# DE-211024_2.net
KiCad netlist of a schematic drawn in Altium Designer
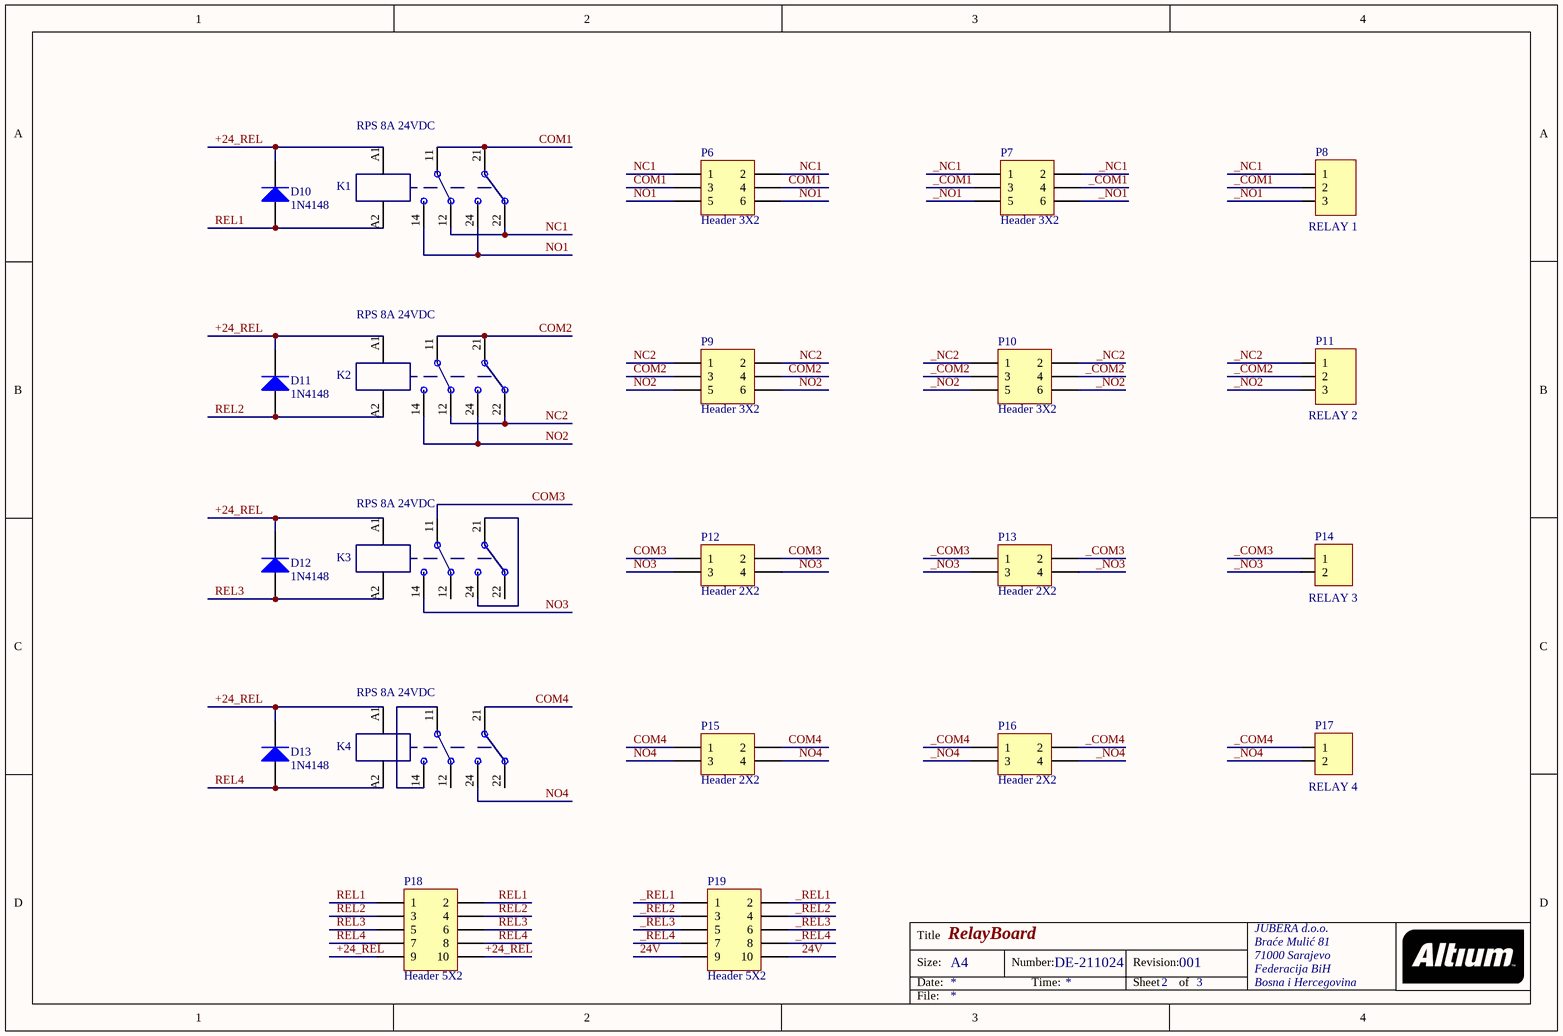
[diagram p0: DE-211024_2.SchDoc]

(export (version "E")
  (design (tool "Eeschema 10.0.6"))
  (components
    (comp (ref "D10")
      (value "1N4148")
      (footprint "SOD323")
      (description "General-purpose Diode")
      (fields (field (name "PUBLISHER") "Altium Limited"))
      (libsource (lib "DE-211024") (part "BAS321"))
    )
    (comp (ref "D11")
      (value "1N4148")
      (footprint "SOD323")
      (description "General-purpose Diode")
      (fields (field (name "PUBLISHER") "Altium Limited"))
      (libsource (lib "DE-211024") (part "BAS321"))
    )
    (comp (ref "D12")
      (value "1N4148")
      (footprint "SOD323")
      (description "General-purpose Diode")
      (fields (field (name "PUBLISHER") "Altium Limited"))
      (libsource (lib "DE-211024") (part "BAS321"))
    )
    (comp (ref "D13")
      (value "1N4148")
      (footprint "SOD323")
      (description "General-purpose Diode")
      (fields (field (name "PUBLISHER") "Altium Limited"))
      (libsource (lib "DE-211024") (part "BAS321"))
    )
    (comp (ref "K1")
      (value "RPS 8A 24VDC")
      (footprint "RPS 2CO 8A 24V")
      (libsource (lib "DE-211024") (part "PCB relay 2CO, 8A, 24VDC, RPS serie 5mm"))
    )
    (comp (ref "K2")
      (value "RPS 8A 24VDC")
      (footprint "RPS 2CO 8A 24V")
      (libsource (lib "DE-211024") (part "PCB relay 2CO, 8A, 24VDC, RPS serie 5mm"))
    )
    (comp (ref "K3")
      (value "RPS 8A 24VDC")
      (footprint "RPS 2CO 8A 24V")
      (libsource (lib "DE-211024") (part "PCB relay 2CO, 8A, 24VDC, RPS serie 5mm"))
    )
    (comp (ref "K4")
      (value "RPS 8A 24VDC")
      (footprint "RPS 2CO 8A 24V")
      (libsource (lib "DE-211024") (part "PCB relay 2CO, 8A, 24VDC, RPS serie 5mm"))
    )
    (comp (ref "P6")
      (value "Header 3X2")
      (footprint "HDR2X3")
      (description "Header, 3-Pin, Dual row")
      (fields (field (name "PUBLISHER") "Altium Limited"))
      (libsource (lib "Miscellaneous Connectors") (part "Header 3X2"))
    )
    (comp (ref "P7")
      (value "Header 3X2")
      (footprint "HDR2X3")
      (description "Header, 3-Pin, Dual row")
      (fields (field (name "PUBLISHER") "Altium Limited"))
      (libsource (lib "Miscellaneous Connectors") (part "Header 3X2"))
    )
    (comp (ref "P8")
      (value "RELAY 1")
      (footprint "TERMINAL BLOK 3")
      (description "3 pinski terminal blok konektor")
      (libsource (lib "DE-211024") (part "TERMINAL BLOK 3"))
    )
    (comp (ref "P9")
      (value "Header 3X2")
      (footprint "HDR2X3")
      (description "Header, 3-Pin, Dual row")
      (fields (field (name "PUBLISHER") "Altium Limited"))
      (libsource (lib "Miscellaneous Connectors") (part "Header 3X2"))
    )
    (comp (ref "P10")
      (value "Header 3X2")
      (footprint "HDR2X3")
      (description "Header, 3-Pin, Dual row")
      (fields (field (name "PUBLISHER") "Altium Limited"))
      (libsource (lib "Miscellaneous Connectors") (part "Header 3X2"))
    )
    (comp (ref "P11")
      (value "RELAY 2")
      (footprint "TERMINAL BLOK 3")
      (description "3 pinski terminal blok konektor")
      (libsource (lib "DE-211024") (part "TERMINAL BLOK 3"))
    )
    (comp (ref "P12")
      (value "Header 2X2")
      (footprint "HDR2X2")
      (description "Header, 2-Pin, Dual row")
      (fields (field (name "PUBLISHER") "Altium Limited"))
      (libsource (lib "Miscellaneous Connectors") (part "Header 2X2"))
    )
    (comp (ref "P13")
      (value "Header 2X2")
      (footprint "HDR2X2")
      (description "Header, 2-Pin, Dual row")
      (fields (field (name "PUBLISHER") "Altium Limited"))
      (libsource (lib "Miscellaneous Connectors") (part "Header 2X2"))
    )
    (comp (ref "P14")
      (value "RELAY 3")
      (footprint "TERMINAL BLOK 2")
      (description "Terminal blok konektor 3,5 mm")
      (libsource (lib "DE-211024") (part "TERMINAL BLOK 2"))
    )
    (comp (ref "P15")
      (value "Header 2X2")
      (footprint "HDR2X2")
      (description "Header, 2-Pin, Dual row")
      (fields (field (name "PUBLISHER") "Altium Limited"))
      (libsource (lib "Miscellaneous Connectors") (part "Header 2X2"))
    )
    (comp (ref "P16")
      (value "Header 2X2")
      (footprint "HDR2X2")
      (description "Header, 2-Pin, Dual row")
      (fields (field (name "PUBLISHER") "Altium Limited"))
      (libsource (lib "Miscellaneous Connectors") (part "Header 2X2"))
    )
    (comp (ref "P17")
      (value "RELAY 4")
      (footprint "TERMINAL BLOK 2")
      (description "Terminal blok konektor 3,5 mm")
      (libsource (lib "DE-211024") (part "TERMINAL BLOK 2"))
    )
    (comp (ref "P18")
      (value "Header 5X2")
      (footprint "HDR2X5")
      (description "Header, 5-Pin, Dual row")
      (fields (field (name "PUBLISHER") "Altium Limited"))
      (libsource (lib "Miscellaneous Connectors") (part "Header 5X2"))
    )
    (comp (ref "P19")
      (value "Header 5X2")
      (footprint "HDR2X5")
      (description "Header, 5-Pin, Dual row")
      (fields (field (name "PUBLISHER") "Altium Limited"))
      (libsource (lib "Miscellaneous Connectors") (part "Header 5X2"))
    )
  )
  (nets
    (net (code "1") (name "/+24_REL") (class "Default")
      (node (ref "D10") (pin "1") (pinfunction "K_1") (pintype "passive"))
      (node (ref "D11") (pin "1") (pinfunction "K_1") (pintype "passive"))
      (node (ref "D12") (pin "1") (pinfunction "K_1") (pintype "passive"))
      (node (ref "D13") (pin "1") (pinfunction "K_1") (pintype "passive"))
      (node (ref "K1") (pin "A1") (pinfunction "1_A1") (pintype "passive"))
      (node (ref "K2") (pin "A1") (pinfunction "1_A1") (pintype "passive"))
      (node (ref "K3") (pin "A1") (pinfunction "1_A1") (pintype "passive"))
      (node (ref "K4") (pin "A1") (pinfunction "1_A1") (pintype "passive"))
      (node (ref "P18") (pin "10") (pinfunction "10_10") (pintype "passive"))
      (node (ref "P18") (pin "9") (pinfunction "9_9") (pintype "passive"))
    )
    (net (code "2") (name "/24V") (class "Default")
      (node (ref "P19") (pin "10") (pinfunction "10_10") (pintype "passive"))
      (node (ref "P19") (pin "9") (pinfunction "9_9") (pintype "passive"))
    )
    (net (code "3") (name "/COM1") (class "Default")
      (node (ref "K1") (pin "11") (pinfunction "3_11") (pintype "passive"))
      (node (ref "K1") (pin "21") (pinfunction "3_21") (pintype "passive"))
      (node (ref "P6") (pin "3") (pinfunction "3_3") (pintype "passive"))
      (node (ref "P6") (pin "4") (pinfunction "4_4") (pintype "passive"))
    )
    (net (code "4") (name "/COM2") (class "Default")
      (node (ref "K2") (pin "11") (pinfunction "3_11") (pintype "passive"))
      (node (ref "K2") (pin "21") (pinfunction "3_21") (pintype "passive"))
      (node (ref "P9") (pin "3") (pinfunction "3_3") (pintype "passive"))
      (node (ref "P9") (pin "4") (pinfunction "4_4") (pintype "passive"))
    )
    (net (code "5") (name "/COM3") (class "Default")
      (node (ref "K3") (pin "11") (pinfunction "3_11") (pintype "passive"))
      (node (ref "P12") (pin "1") (pinfunction "1_1") (pintype "passive"))
      (node (ref "P12") (pin "2") (pinfunction "2_2") (pintype "passive"))
    )
    (net (code "6") (name "/COM4") (class "Default")
      (node (ref "K4") (pin "21") (pinfunction "3_21") (pintype "passive"))
      (node (ref "P15") (pin "1") (pinfunction "1_1") (pintype "passive"))
      (node (ref "P15") (pin "2") (pinfunction "2_2") (pintype "passive"))
    )
    (net (code "7") (name "/NC1") (class "Default")
      (node (ref "K1") (pin "12") (pinfunction "5_12") (pintype "passive"))
      (node (ref "K1") (pin "22") (pinfunction "5_22") (pintype "passive"))
      (node (ref "P6") (pin "1") (pinfunction "1_1") (pintype "passive"))
      (node (ref "P6") (pin "2") (pinfunction "2_2") (pintype "passive"))
    )
    (net (code "8") (name "/NC2") (class "Default")
      (node (ref "K2") (pin "12") (pinfunction "5_12") (pintype "passive"))
      (node (ref "K2") (pin "22") (pinfunction "5_22") (pintype "passive"))
      (node (ref "P9") (pin "1") (pinfunction "1_1") (pintype "passive"))
      (node (ref "P9") (pin "2") (pinfunction "2_2") (pintype "passive"))
    )
    (net (code "9") (name "/NO1") (class "Default")
      (node (ref "K1") (pin "14") (pinfunction "4_14") (pintype "passive"))
      (node (ref "K1") (pin "24") (pinfunction "4_24") (pintype "passive"))
      (node (ref "P6") (pin "5") (pinfunction "5_5") (pintype "passive"))
      (node (ref "P6") (pin "6") (pinfunction "6_6") (pintype "passive"))
    )
    (net (code "10") (name "/NO2") (class "Default")
      (node (ref "K2") (pin "14") (pinfunction "4_14") (pintype "passive"))
      (node (ref "K2") (pin "24") (pinfunction "4_24") (pintype "passive"))
      (node (ref "P9") (pin "5") (pinfunction "5_5") (pintype "passive"))
      (node (ref "P9") (pin "6") (pinfunction "6_6") (pintype "passive"))
    )
    (net (code "11") (name "/NO3") (class "Default")
      (node (ref "K3") (pin "14") (pinfunction "4_14") (pintype "passive"))
      (node (ref "P12") (pin "3") (pinfunction "3_3") (pintype "passive"))
      (node (ref "P12") (pin "4") (pinfunction "4_4") (pintype "passive"))
    )
    (net (code "12") (name "/NO4") (class "Default")
      (node (ref "K4") (pin "24") (pinfunction "4_24") (pintype "passive"))
      (node (ref "P15") (pin "3") (pinfunction "3_3") (pintype "passive"))
      (node (ref "P15") (pin "4") (pinfunction "4_4") (pintype "passive"))
    )
    (net (code "13") (name "/REL1") (class "Default")
      (node (ref "D10") (pin "2") (pinfunction "A_2") (pintype "passive"))
      (node (ref "K1") (pin "A2") (pinfunction "2_A2") (pintype "passive"))
      (node (ref "P18") (pin "1") (pinfunction "1_1") (pintype "passive"))
      (node (ref "P18") (pin "2") (pinfunction "2_2") (pintype "passive"))
    )
    (net (code "14") (name "/REL2") (class "Default")
      (node (ref "D11") (pin "2") (pinfunction "A_2") (pintype "passive"))
      (node (ref "K2") (pin "A2") (pinfunction "2_A2") (pintype "passive"))
      (node (ref "P18") (pin "3") (pinfunction "3_3") (pintype "passive"))
      (node (ref "P18") (pin "4") (pinfunction "4_4") (pintype "passive"))
    )
    (net (code "15") (name "/REL3") (class "Default")
      (node (ref "D12") (pin "2") (pinfunction "A_2") (pintype "passive"))
      (node (ref "K3") (pin "A2") (pinfunction "2_A2") (pintype "passive"))
      (node (ref "P18") (pin "5") (pinfunction "5_5") (pintype "passive"))
      (node (ref "P18") (pin "6") (pinfunction "6_6") (pintype "passive"))
    )
    (net (code "16") (name "/REL4") (class "Default")
      (node (ref "D13") (pin "2") (pinfunction "A_2") (pintype "passive"))
      (node (ref "K4") (pin "A2") (pinfunction "2_A2") (pintype "passive"))
      (node (ref "P18") (pin "7") (pinfunction "7_7") (pintype "passive"))
      (node (ref "P18") (pin "8") (pinfunction "8_8") (pintype "passive"))
    )
    (net (code "17") (name "/_COM1") (class "Default")
      (node (ref "P7") (pin "3") (pinfunction "3_3") (pintype "passive"))
      (node (ref "P7") (pin "4") (pinfunction "4_4") (pintype "passive"))
      (node (ref "P8") (pin "2") (pinfunction "2_2") (pintype "passive"))
    )
    (net (code "18") (name "/_COM2") (class "Default")
      (node (ref "P10") (pin "3") (pinfunction "3_3") (pintype "passive"))
      (node (ref "P10") (pin "4") (pinfunction "4_4") (pintype "passive"))
      (node (ref "P11") (pin "2") (pinfunction "2_2") (pintype "passive"))
    )
    (net (code "19") (name "/_COM3") (class "Default")
      (node (ref "P13") (pin "1") (pinfunction "1_1") (pintype "passive"))
      (node (ref "P13") (pin "2") (pinfunction "2_2") (pintype "passive"))
      (node (ref "P14") (pin "1") (pinfunction "1_1") (pintype "passive"))
    )
    (net (code "20") (name "/_COM4") (class "Default")
      (node (ref "P16") (pin "1") (pinfunction "1_1") (pintype "passive"))
      (node (ref "P16") (pin "2") (pinfunction "2_2") (pintype "passive"))
      (node (ref "P17") (pin "1") (pinfunction "1_1") (pintype "passive"))
    )
    (net (code "21") (name "/_NC1") (class "Default")
      (node (ref "P7") (pin "1") (pinfunction "1_1") (pintype "passive"))
      (node (ref "P7") (pin "2") (pinfunction "2_2") (pintype "passive"))
      (node (ref "P8") (pin "1") (pinfunction "1_1") (pintype "passive"))
    )
    (net (code "22") (name "/_NC2") (class "Default")
      (node (ref "P10") (pin "1") (pinfunction "1_1") (pintype "passive"))
      (node (ref "P10") (pin "2") (pinfunction "2_2") (pintype "passive"))
      (node (ref "P11") (pin "1") (pinfunction "1_1") (pintype "passive"))
    )
    (net (code "23") (name "/_NO1") (class "Default")
      (node (ref "P7") (pin "5") (pinfunction "5_5") (pintype "passive"))
      (node (ref "P7") (pin "6") (pinfunction "6_6") (pintype "passive"))
      (node (ref "P8") (pin "3") (pinfunction "3_3") (pintype "passive"))
    )
    (net (code "24") (name "/_NO2") (class "Default")
      (node (ref "P10") (pin "5") (pinfunction "5_5") (pintype "passive"))
      (node (ref "P10") (pin "6") (pinfunction "6_6") (pintype "passive"))
      (node (ref "P11") (pin "3") (pinfunction "3_3") (pintype "passive"))
    )
    (net (code "25") (name "/_NO3") (class "Default")
      (node (ref "P13") (pin "3") (pinfunction "3_3") (pintype "passive"))
      (node (ref "P13") (pin "4") (pinfunction "4_4") (pintype "passive"))
      (node (ref "P14") (pin "2") (pinfunction "2_2") (pintype "passive"))
    )
    (net (code "26") (name "/_NO4") (class "Default")
      (node (ref "P16") (pin "3") (pinfunction "3_3") (pintype "passive"))
      (node (ref "P16") (pin "4") (pinfunction "4_4") (pintype "passive"))
      (node (ref "P17") (pin "2") (pinfunction "2_2") (pintype "passive"))
    )
    (net (code "27") (name "/_REL1") (class "Default")
      (node (ref "P19") (pin "1") (pinfunction "1_1") (pintype "passive"))
      (node (ref "P19") (pin "2") (pinfunction "2_2") (pintype "passive"))
    )
    (net (code "28") (name "/_REL2") (class "Default")
      (node (ref "P19") (pin "3") (pinfunction "3_3") (pintype "passive"))
      (node (ref "P19") (pin "4") (pinfunction "4_4") (pintype "passive"))
    )
    (net (code "29") (name "/_REL3") (class "Default")
      (node (ref "P19") (pin "5") (pinfunction "5_5") (pintype "passive"))
      (node (ref "P19") (pin "6") (pinfunction "6_6") (pintype "passive"))
    )
    (net (code "30") (name "/_REL4") (class "Default")
      (node (ref "P19") (pin "7") (pinfunction "7_7") (pintype "passive"))
      (node (ref "P19") (pin "8") (pinfunction "8_8") (pintype "passive"))
    )
    (net (code "31") (name "Net-(K3-3-Pad21)") (class "Default")
      (node (ref "K3") (pin "21") (pinfunction "3_21") (pintype "passive"))
      (node (ref "K3") (pin "24") (pinfunction "4_24") (pintype "passive"))
    )
    (net (code "32") (name "Net-(K4-3-Pad11)") (class "Default")
      (node (ref "K4") (pin "11") (pinfunction "3_11") (pintype "passive"))
      (node (ref "K4") (pin "14") (pinfunction "4_14") (pintype "passive"))
    )
    (net (code "33") (name "unconnected-(K3-5-Pad12)") (class "Default")
      (node (ref "K3") (pin "12") (pinfunction "5_12") (pintype "passive"))
    )
    (net (code "34") (name "unconnected-(K3-5-Pad22)") (class "Default")
      (node (ref "K3") (pin "22") (pinfunction "5_22") (pintype "passive"))
    )
    (net (code "35") (name "unconnected-(K4-5-Pad12)") (class "Default")
      (node (ref "K4") (pin "12") (pinfunction "5_12") (pintype "passive"))
    )
    (net (code "36") (name "unconnected-(K4-5-Pad22)") (class "Default")
      (node (ref "K4") (pin "22") (pinfunction "5_22") (pintype "passive"))
    )
  )
)
